# ToFBoard.net
KiCad netlist of a schematic drawn in Altium Designer
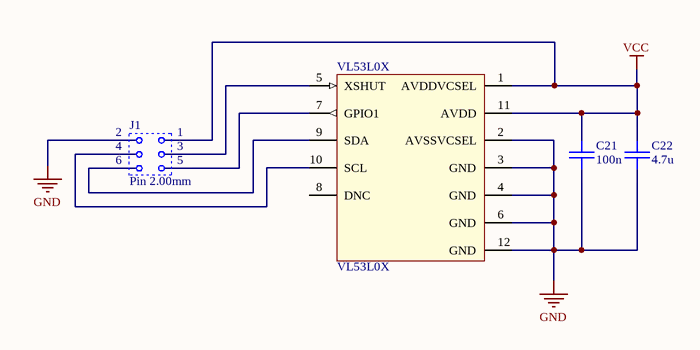
[diagram p0: ToFBoard.SchDoc]

(export (version "E")
  (design (tool "Eeschema 10.0.6"))
  (components
    (comp (ref "C21")
      (value "100n")
      (footprint "Other-Discrete:0805")
      (description "Ceramic Capacitor")
      (libsource (lib "Disc-Other") (part "C_CER"))
    )
    (comp (ref "C22")
      (value "4.7u")
      (footprint "Other-Discrete:0805")
      (description "Ceramic Capacitor")
      (libsource (lib "Disc-Other") (part "C_CER"))
    )
    (comp (ref "J1")
      (value "Pin 2.00mm")
      (footprint "Other-Connectors:Goldpin 2.00mm pin 2X3")
      (libsource (lib "Connectors") (part "Goldpin 2.00 pin 2x3"))
    )
    (comp (ref "VL53L0X")
      (value "VL53L0X")
      (description "Time-of-Flight ranging and gesture detection sensor")
      (libsource (lib "rys_component_lib") (part "VL53L0X ToF"))
    )
  )
  (nets
    (net (code "1") (name "GND") (class "Default")
      (node (ref "C21") (pin "2") (pinfunction "2_2") (pintype "passive"))
      (node (ref "C22") (pin "2") (pinfunction "2_2") (pintype "passive"))
      (node (ref "J1") (pin "2") (pintype "passive"))
      (node (ref "VL53L0X") (pin "12") (pinfunction "GND_12") (pintype "passive"))
      (node (ref "VL53L0X") (pin "2") (pinfunction "AVSSVCSEL_2") (pintype "passive"))
      (node (ref "VL53L0X") (pin "3") (pinfunction "GND_3") (pintype "passive"))
      (node (ref "VL53L0X") (pin "4") (pinfunction "GND_4") (pintype "passive"))
      (node (ref "VL53L0X") (pin "6") (pinfunction "GND_6") (pintype "passive"))
    )
    (net (code "2") (name "Net-(VL53L0X-GPIO1)") (class "Default")
      (node (ref "J1") (pin "5") (pintype "passive"))
      (node (ref "VL53L0X") (pin "7") (pinfunction "GPIO1_7") (pintype "output"))
    )
    (net (code "3") (name "Net-(VL53L0X-SCL)") (class "Default")
      (node (ref "J1") (pin "4") (pintype "passive"))
      (node (ref "VL53L0X") (pin "10") (pinfunction "SCL_10") (pintype "passive"))
    )
    (net (code "4") (name "Net-(VL53L0X-SDA)") (class "Default")
      (node (ref "J1") (pin "6") (pintype "passive"))
      (node (ref "VL53L0X") (pin "9") (pinfunction "SDA_9") (pintype "passive"))
    )
    (net (code "5") (name "Net-(VL53L0X-XSHUT)") (class "Default")
      (node (ref "J1") (pin "3") (pintype "passive"))
      (node (ref "VL53L0X") (pin "5") (pinfunction "XSHUT_5") (pintype "input"))
    )
    (net (code "6") (name "VCC") (class "Default")
      (node (ref "C21") (pin "1") (pinfunction "1_1") (pintype "passive"))
      (node (ref "C22") (pin "1") (pinfunction "1_1") (pintype "passive"))
      (node (ref "J1") (pin "1") (pintype "passive"))
      (node (ref "VL53L0X") (pin "1") (pinfunction "AVDDVCSEL_1") (pintype "passive"))
      (node (ref "VL53L0X") (pin "11") (pinfunction "AVDD_11") (pintype "passive"))
    )
    (net (code "7") (name "unconnected-(VL53L0X-DNC-Pad8)") (class "Default")
      (node (ref "VL53L0X") (pin "8") (pinfunction "DNC_8") (pintype "passive"))
    )
  )
)
